# bbf-europower.net
KiCad netlist of a schematic drawn in EAGLE
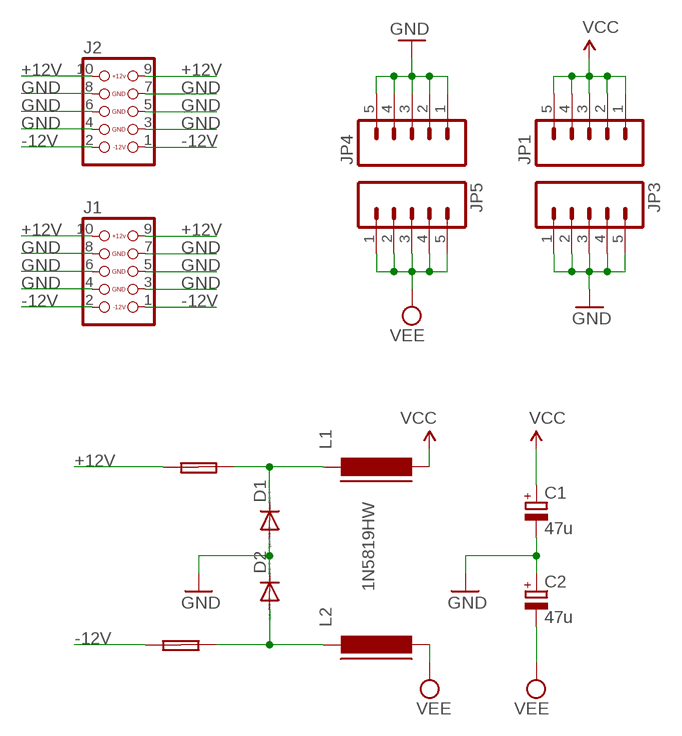
[diagram p0: schematic, sheet 1]

(export (version "E")
  (design (tool "Eeschema 10.0.6"))
  (components
    (comp (ref "+FUSE1")
      (value "+FUSE")
      (footprint "eagle-import:C050H075X075")
      (libsource (lib "eagle-import") (part "PTC_FUSEPOLY_FUSE"))
    )
    (comp (ref "-FUSE1")
      (value "-FUSE")
      (footprint "eagle-import:C050H075X075")
      (libsource (lib "eagle-import") (part "PTC_FUSEPOLY_FUSE"))
    )
    (comp (ref "C1")
      (value "47u")
      (footprint "eagle-import:E2-5")
      (libsource (lib "eagle-import") (part "CPOL-EUE2-5"))
    )
    (comp (ref "C2")
      (value "47u")
      (footprint "eagle-import:E2-5")
      (libsource (lib "eagle-import") (part "CPOL-EUE2-5"))
    )
    (comp (ref "D1")
      (value "1N5819HW")
      (footprint "eagle-import:DO35-7")
      (libsource (lib "eagle-import") (part "1N4148DO35-7"))
    )
    (comp (ref "D2")
      (value "1N5819HW")
      (footprint "eagle-import:DO35-7")
      (libsource (lib "eagle-import") (part "1N4148DO35-7"))
    )
    (comp (ref "J1")
      (value "CON_HEADER_2X05-PTH")
      (footprint "eagle-import:M2X5")
      (libsource (lib "eagle-import") (part "CON_HEADER_2X05-PTH"))
    )
    (comp (ref "J2")
      (value "CON_HEADER_2X05-PTH")
      (footprint "eagle-import:M2X5")
      (libsource (lib "eagle-import") (part "CON_HEADER_2X05-PTH"))
    )
    (comp (ref "JP1")
      (value "M05PTH")
      (footprint "eagle-import:1X05")
      (libsource (lib "eagle-import") (part "M05PTH"))
    )
    (comp (ref "JP3")
      (value "M05PTH")
      (footprint "eagle-import:1X05")
      (libsource (lib "eagle-import") (part "M05PTH"))
    )
    (comp (ref "JP4")
      (value "M05PTH")
      (footprint "eagle-import:1X05")
      (libsource (lib "eagle-import") (part "M05PTH"))
    )
    (comp (ref "JP5")
      (value "M05PTH")
      (footprint "eagle-import:1X05")
      (libsource (lib "eagle-import") (part "M05PTH"))
    )
    (comp (ref "L1")
      (value "FERRITE-SHORT")
      (footprint "eagle-import:FBS")
      (libsource (lib "eagle-import") (part "FERRITE-SHORT"))
    )
    (comp (ref "L2")
      (value "FERRITE-SHORT")
      (footprint "eagle-import:FBS")
      (libsource (lib "eagle-import") (part "FERRITE-SHORT"))
    )
  )
  (nets
    (net (code "1") (name "/+12V") (class "Default")
      (node (ref "+FUSE1") (pin "1") (pinfunction "P$1_1") (pintype "bidirectional"))
      (node (ref "J1") (pin "10") (pinfunction "10_10") (pintype "passive"))
      (node (ref "J1") (pin "9") (pinfunction "9_9") (pintype "passive"))
      (node (ref "J2") (pin "10") (pinfunction "10_10") (pintype "passive"))
      (node (ref "J2") (pin "9") (pinfunction "9_9") (pintype "passive"))
    )
    (net (code "2") (name "/-12V") (class "Default")
      (node (ref "-FUSE1") (pin "1") (pinfunction "P$1_1") (pintype "bidirectional"))
      (node (ref "J1") (pin "1") (pinfunction "1_1") (pintype "passive"))
      (node (ref "J1") (pin "2") (pinfunction "2_2") (pintype "passive"))
      (node (ref "J2") (pin "1") (pinfunction "1_1") (pintype "passive"))
      (node (ref "J2") (pin "2") (pinfunction "2_2") (pintype "passive"))
    )
    (net (code "3") (name "GND") (class "Default")
      (node (ref "C1") (pin "-") (pinfunction "-_-") (pintype "passive"))
      (node (ref "C2") (pin "+") (pinfunction "+_+") (pintype "passive"))
      (node (ref "D1") (pin "A") (pinfunction "A_A") (pintype "passive"))
      (node (ref "D2") (pin "C") (pinfunction "C_C") (pintype "passive"))
      (node (ref "J1") (pin "3") (pinfunction "3_3") (pintype "passive"))
      (node (ref "J1") (pin "4") (pinfunction "4_4") (pintype "passive"))
      (node (ref "J1") (pin "5") (pinfunction "5_5") (pintype "passive"))
      (node (ref "J1") (pin "6") (pinfunction "6_6") (pintype "passive"))
      (node (ref "J1") (pin "7") (pinfunction "7_7") (pintype "passive"))
      (node (ref "J1") (pin "8") (pinfunction "8_8") (pintype "passive"))
      (node (ref "J2") (pin "3") (pinfunction "3_3") (pintype "passive"))
      (node (ref "J2") (pin "4") (pinfunction "4_4") (pintype "passive"))
      (node (ref "J2") (pin "5") (pinfunction "5_5") (pintype "passive"))
      (node (ref "J2") (pin "6") (pinfunction "6_6") (pintype "passive"))
      (node (ref "J2") (pin "7") (pinfunction "7_7") (pintype "passive"))
      (node (ref "J2") (pin "8") (pinfunction "8_8") (pintype "passive"))
      (node (ref "JP3") (pin "1") (pinfunction "1_1") (pintype "passive"))
      (node (ref "JP3") (pin "2") (pinfunction "2_2") (pintype "passive"))
      (node (ref "JP3") (pin "3") (pinfunction "3_3") (pintype "passive"))
      (node (ref "JP3") (pin "4") (pinfunction "4_4") (pintype "passive"))
      (node (ref "JP3") (pin "5") (pinfunction "5_5") (pintype "passive"))
      (node (ref "JP4") (pin "1") (pinfunction "1_1") (pintype "passive"))
      (node (ref "JP4") (pin "2") (pinfunction "2_2") (pintype "passive"))
      (node (ref "JP4") (pin "3") (pinfunction "3_3") (pintype "passive"))
      (node (ref "JP4") (pin "4") (pinfunction "4_4") (pintype "passive"))
      (node (ref "JP4") (pin "5") (pinfunction "5_5") (pintype "passive"))
    )
    (net (code "4") (name "Net-(+FUSE1-P$2)") (class "Default")
      (node (ref "+FUSE1") (pin "2") (pinfunction "P$2_2") (pintype "bidirectional"))
      (node (ref "D1") (pin "C") (pinfunction "C_C") (pintype "passive"))
      (node (ref "L1") (pin "1") (pinfunction "1_1") (pintype "passive"))
    )
    (net (code "5") (name "Net-(-FUSE1-P$2)") (class "Default")
      (node (ref "-FUSE1") (pin "2") (pinfunction "P$2_2") (pintype "bidirectional"))
      (node (ref "D2") (pin "A") (pinfunction "A_A") (pintype "passive"))
      (node (ref "L2") (pin "1") (pinfunction "1_1") (pintype "passive"))
    )
    (net (code "6") (name "VCC") (class "Default")
      (node (ref "C1") (pin "+") (pinfunction "+_+") (pintype "passive"))
      (node (ref "JP1") (pin "1") (pinfunction "1_1") (pintype "passive"))
      (node (ref "JP1") (pin "2") (pinfunction "2_2") (pintype "passive"))
      (node (ref "JP1") (pin "3") (pinfunction "3_3") (pintype "passive"))
      (node (ref "JP1") (pin "4") (pinfunction "4_4") (pintype "passive"))
      (node (ref "JP1") (pin "5") (pinfunction "5_5") (pintype "passive"))
      (node (ref "L1") (pin "2") (pinfunction "2_2") (pintype "passive"))
    )
    (net (code "7") (name "VEE") (class "Default")
      (node (ref "C2") (pin "-") (pinfunction "-_-") (pintype "passive"))
      (node (ref "JP5") (pin "1") (pinfunction "1_1") (pintype "passive"))
      (node (ref "JP5") (pin "2") (pinfunction "2_2") (pintype "passive"))
      (node (ref "JP5") (pin "3") (pinfunction "3_3") (pintype "passive"))
      (node (ref "JP5") (pin "4") (pinfunction "4_4") (pintype "passive"))
      (node (ref "JP5") (pin "5") (pinfunction "5_5") (pintype "passive"))
      (node (ref "L2") (pin "2") (pinfunction "2_2") (pintype "passive"))
    )
  )
)
